# BSPDSchematic.net
KiCad netlist of a schematic drawn in Altium Designer
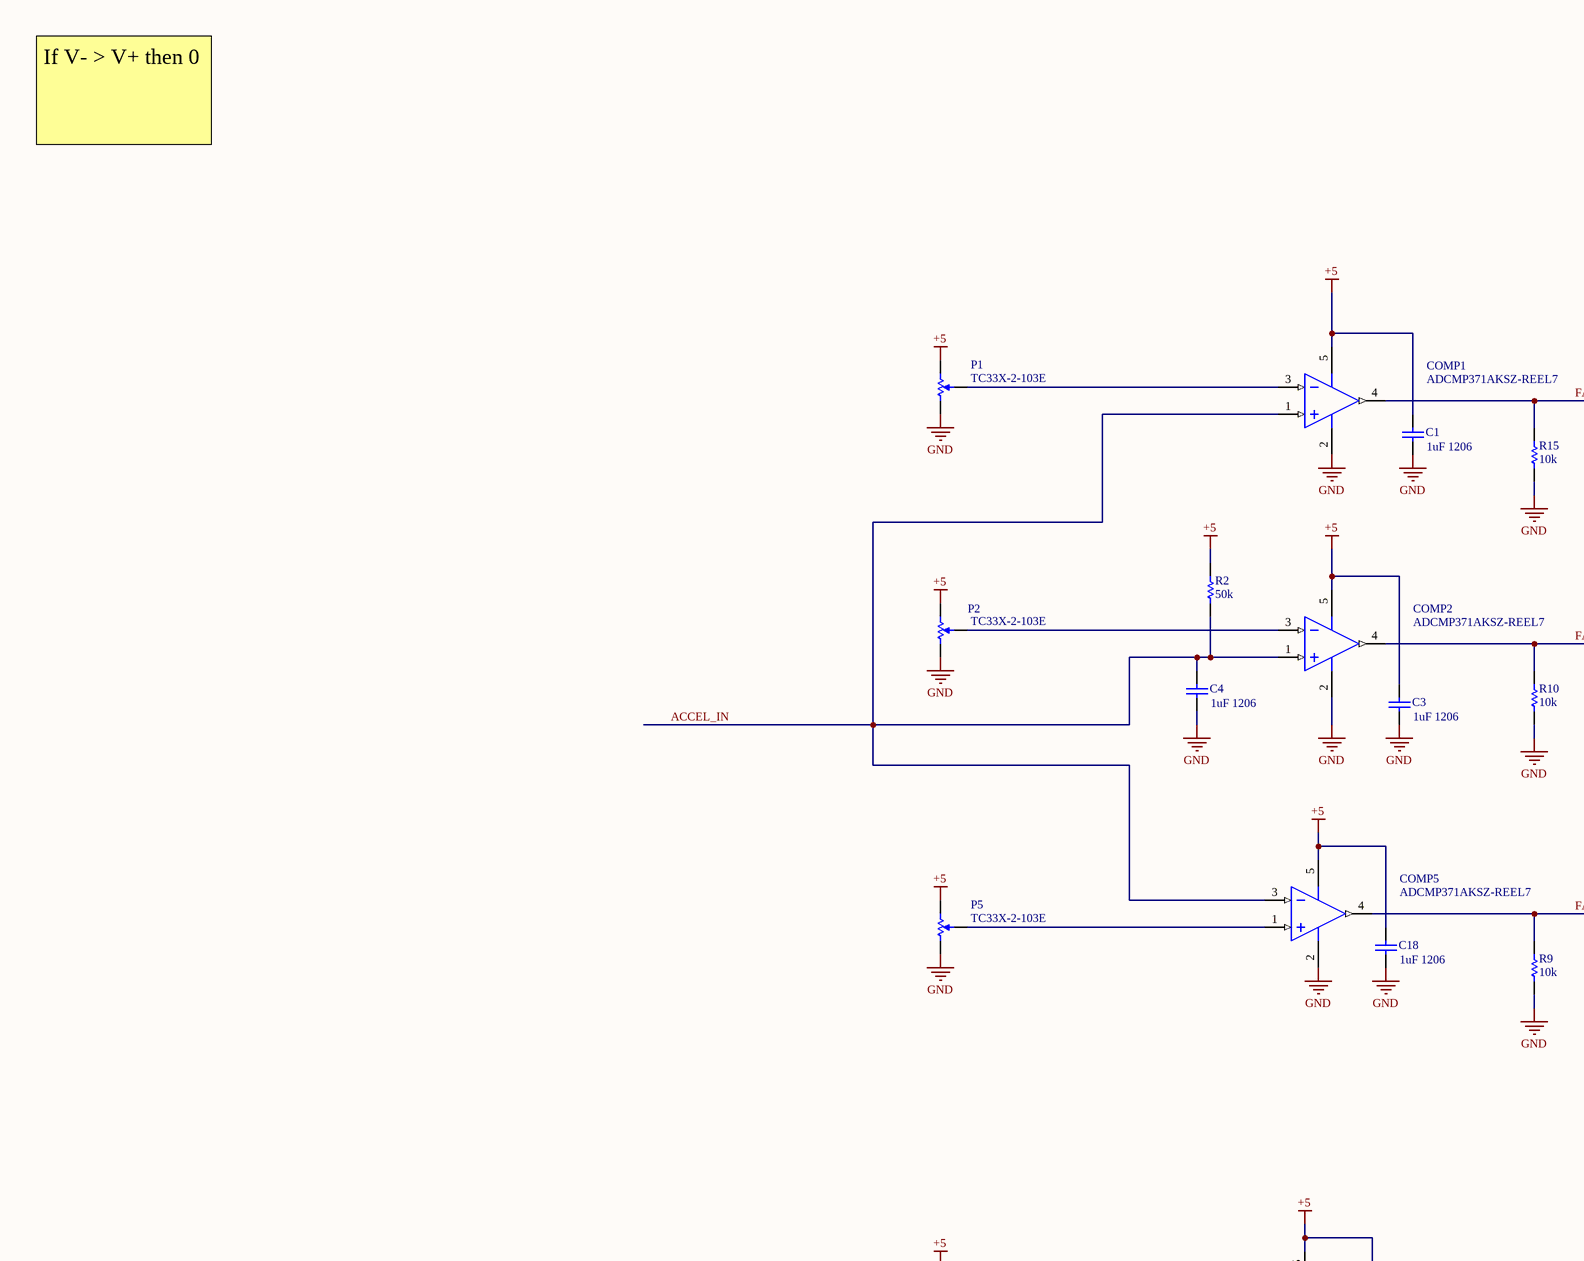
[diagram p0: BSPDSchematic.SchDoc, top left]
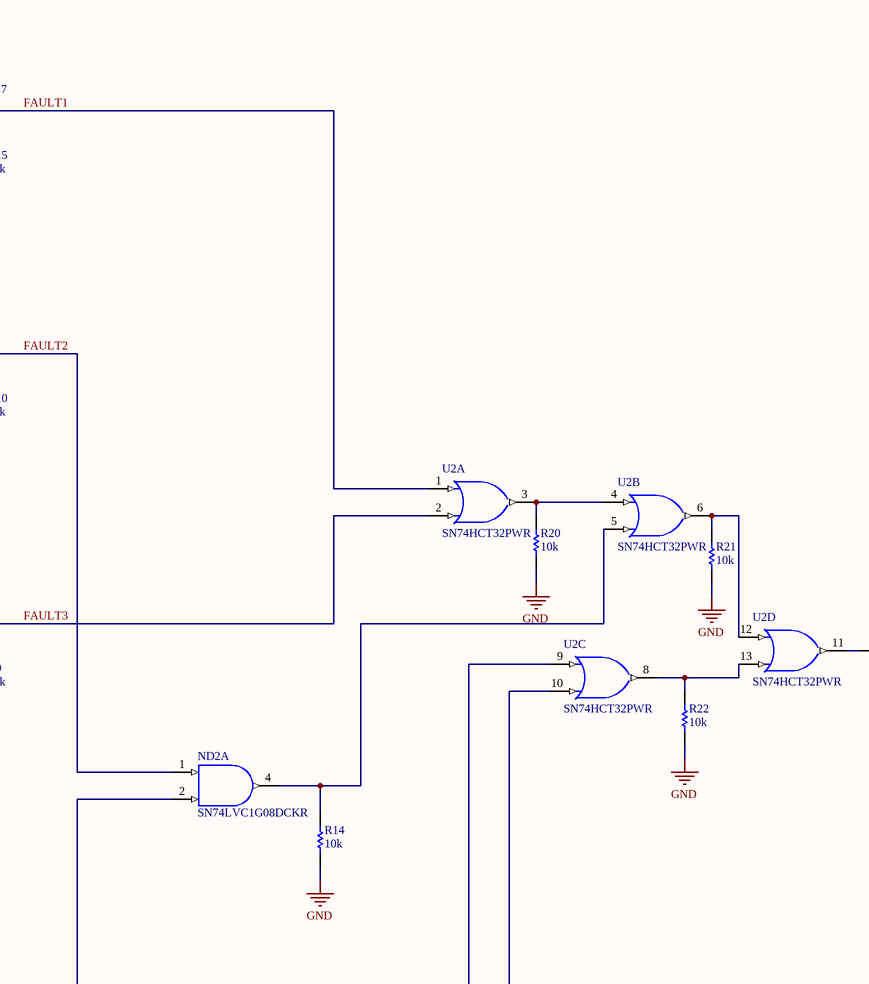
[diagram p1: BSPDSchematic.SchDoc, top middle]
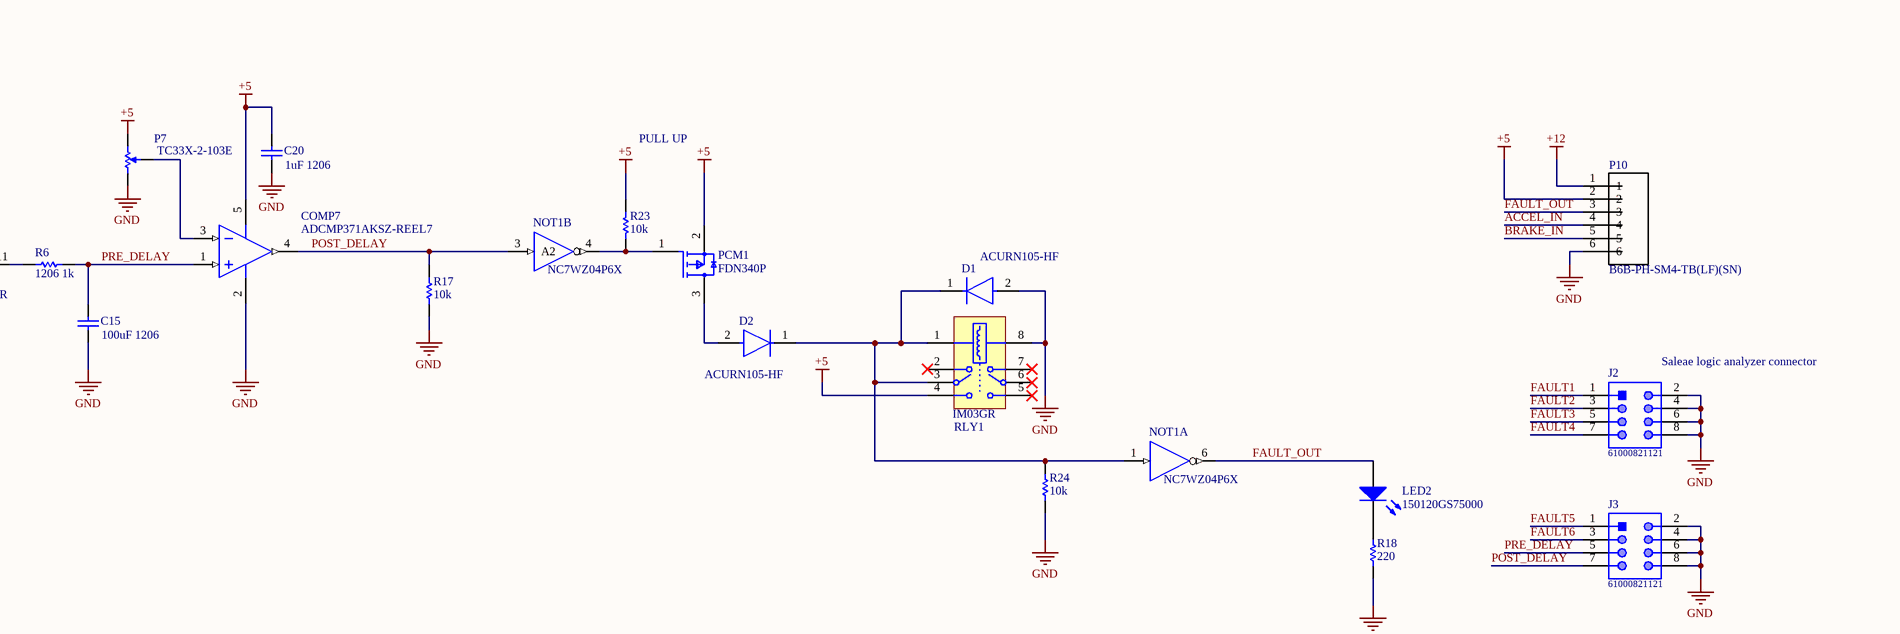
[diagram p2: BSPDSchematic.SchDoc, top right]
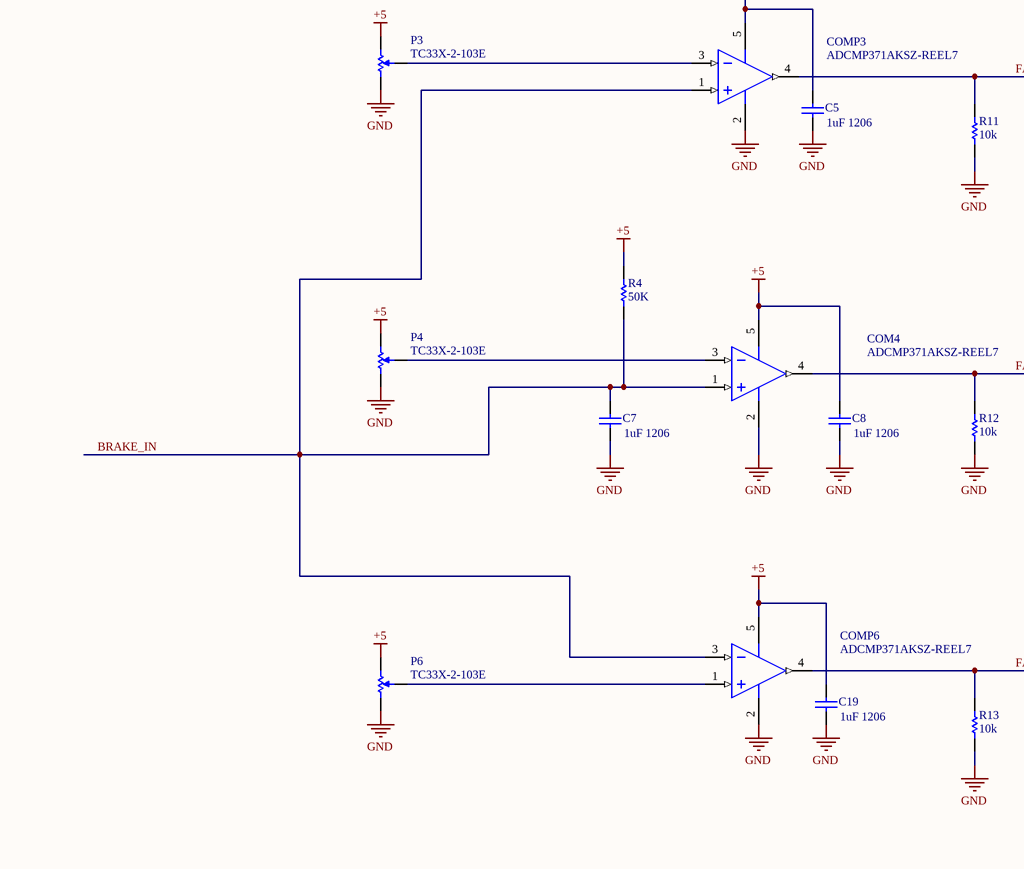
[diagram p3: BSPDSchematic.SchDoc, bottom left]
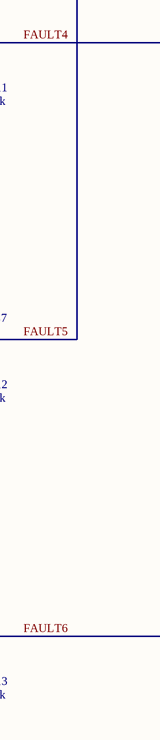
[diagram p4: BSPDSchematic.SchDoc, bottom middle]
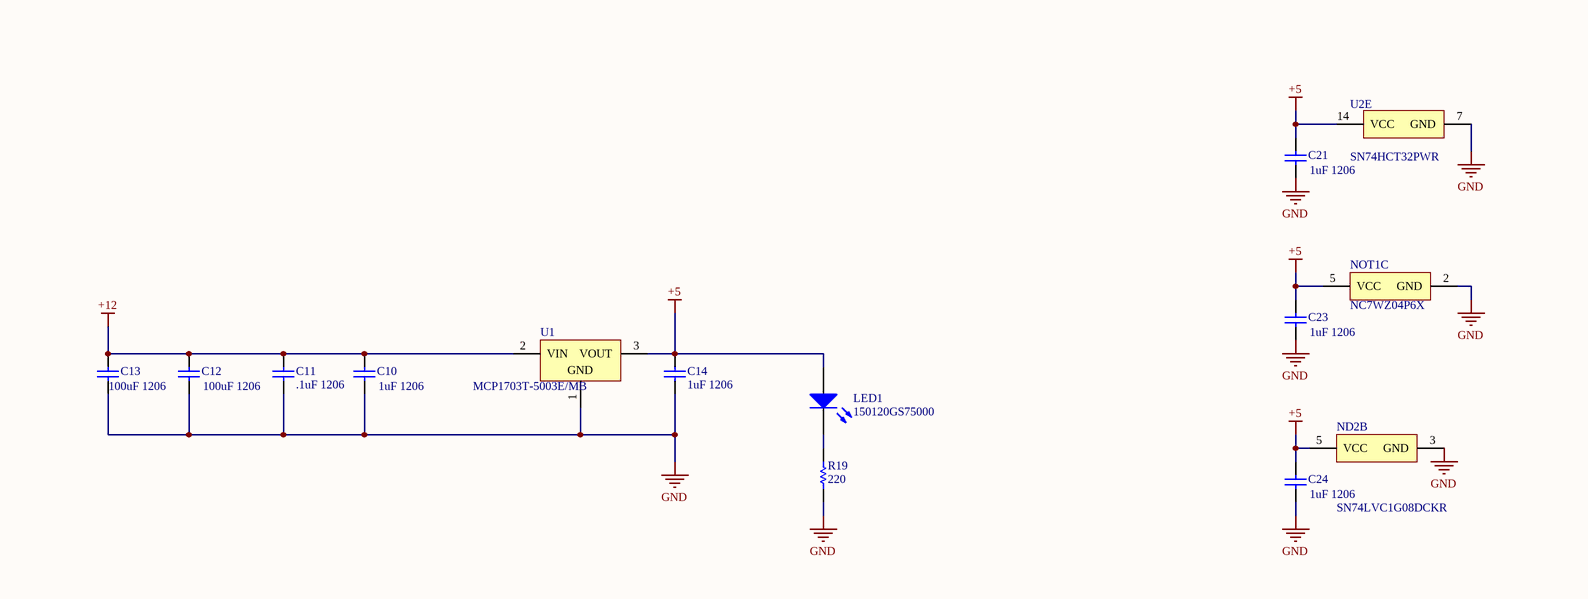
[diagram p5: BSPDSchematic.SchDoc, bottom right]

(export (version "E")
  (design (tool "Eeschema 10.0.6"))
  (components
    (comp (ref "C1")
      (value "1uF 1206")
      (footprint "CAPC3216X152X50LL20T25")
      (description "Chip Capacitor, 330 nF, +/- 10%, 50 V, -55 to 125 degC, 1206 (3216 Metric), RoHS, Tape and Reel")
      (fields (field (name "MANUFACTURER") "AVX"))
      (libsource (lib "Altium Content Vault") (part "CAP-NP-2"))
    )
    (comp (ref "C3")
      (value "1uF 1206")
      (footprint "CAPC3216X152X50LL20T25")
      (description "Chip Capacitor, 330 nF, +/- 10%, 50 V, -55 to 125 degC, 1206 (3216 Metric), RoHS, Tape and Reel")
      (fields (field (name "MANUFACTURER") "AVX"))
      (libsource (lib "Altium Content Vault") (part "CAP-NP-2"))
    )
    (comp (ref "C4")
      (value "1uF 1206")
      (footprint "CAPC3216X152X50LL20T25")
      (description "Chip Capacitor, 330 nF, +/- 10%, 50 V, -55 to 125 degC, 1206 (3216 Metric), RoHS, Tape and Reel")
      (fields (field (name "MANUFACTURER") "AVX"))
      (libsource (lib "Altium Content Vault") (part "CAP-NP-2"))
    )
    (comp (ref "C5")
      (value "1uF 1206")
      (footprint "CAPC3216X152X50LL20T25")
      (description "Chip Capacitor, 330 nF, +/- 10%, 50 V, -55 to 125 degC, 1206 (3216 Metric), RoHS, Tape and Reel")
      (fields (field (name "MANUFACTURER") "AVX"))
      (libsource (lib "Altium Content Vault") (part "CAP-NP-2"))
    )
    (comp (ref "C7")
      (value "1uF 1206")
      (footprint "CAPC3216X152X50LL20T25")
      (description "Chip Capacitor, 330 nF, +/- 10%, 50 V, -55 to 125 degC, 1206 (3216 Metric), RoHS, Tape and Reel")
      (fields (field (name "MANUFACTURER") "AVX"))
      (libsource (lib "Altium Content Vault") (part "CAP-NP-2"))
    )
    (comp (ref "C8")
      (value "1uF 1206")
      (footprint "CAPC3216X152X50LL20T25")
      (description "Chip Capacitor, 330 nF, +/- 10%, 50 V, -55 to 125 degC, 1206 (3216 Metric), RoHS, Tape and Reel")
      (fields (field (name "MANUFACTURER") "AVX"))
      (libsource (lib "Altium Content Vault") (part "CAP-NP-2"))
    )
    (comp (ref "C10")
      (value "1uF 1206")
      (footprint "CAPC3216X152X50LL20T25")
      (description "Chip Capacitor, 330 nF, +/- 10%, 50 V, -55 to 125 degC, 1206 (3216 Metric), RoHS, Tape and Reel")
      (fields (field (name "MANUFACTURER") "AVX"))
      (libsource (lib "Altium Content Vault") (part "CAP-NP-2"))
    )
    (comp (ref "C11")
      (value ".1uF 1206")
      (footprint "CAPC1206(3216)190_L")
      (description "CAP 100uF 6.3V ±20% 1206 (3216 Metric) Thickness 1.9mm SMD")
      (fields (field (name "TOLERANCE") "Â±20%"))
      (libsource (lib "Altium Content Vault") (part "CAP"))
    )
    (comp (ref "C12")
      (value "100uF 1206")
      (footprint "CAPC1206(3216)190_L")
      (description "CAP 100uF 6.3V ±20% 1206 (3216 Metric) Thickness 1.9mm SMD")
      (fields (field (name "TOLERANCE") "Â±20%"))
      (libsource (lib "Altium Content Vault") (part "CAP"))
    )
    (comp (ref "C13")
      (value "100uF 1206")
      (footprint "CAPC3216X180X50LL20T25")
      (description "Chip Capacitor, 2.2 uF, +/- 10%, 16 V, -55 to 125 degC, 1206 (3216 Metric), RoHS, Tape and Reel")
      (fields (field (name "TOLERANCE") "10%") (field (name "MANUFACTURER") "Kemet"))
      (libsource (lib "Altium Content Vault") (part "CAP-NP-2"))
    )
    (comp (ref "C14")
      (value "1uF 1206")
      (footprint "CAPC3216X180X50ML20T25")
      (description "Chip Capacitor, 1 uF, +/- 10%, 25 V, -55 to 125 degC, 1206 (3216 Metric), RoHS, Tape and Reel")
      (fields (field (name "MANUFACTURER") "Kemet") (field (name "TOLERANCE") "10%"))
      (libsource (lib "Altium Content Vault") (part "CAP-NP-2"))
    )
    (comp (ref "C15")
      (value "100uF 1206")
      (footprint "CAPC3216X152X50LL20T25")
      (description "Chip Capacitor, 330 nF, +/- 10%, 50 V, -55 to 125 degC, 1206 (3216 Metric), RoHS, Tape and Reel")
      (fields (field (name "MANUFACTURER") "AVX"))
      (libsource (lib "Altium Content Vault") (part "CAP-NP-2"))
    )
    (comp (ref "C18")
      (value "1uF 1206")
      (footprint "CAPC3216X152X50LL20T25")
      (description "Chip Capacitor, 330 nF, +/- 10%, 50 V, -55 to 125 degC, 1206 (3216 Metric), RoHS, Tape and Reel")
      (fields (field (name "MANUFACTURER") "AVX"))
      (libsource (lib "Altium Content Vault") (part "CAP-NP-2"))
    )
    (comp (ref "C19")
      (value "1uF 1206")
      (footprint "CAPC3216X152X50LL20T25")
      (description "Chip Capacitor, 330 nF, +/- 10%, 50 V, -55 to 125 degC, 1206 (3216 Metric), RoHS, Tape and Reel")
      (fields (field (name "MANUFACTURER") "AVX"))
      (libsource (lib "Altium Content Vault") (part "CAP-NP-2"))
    )
    (comp (ref "C20")
      (value "1uF 1206")
      (footprint "CAPC3216X152X50LL20T25")
      (description "Chip Capacitor, 330 nF, +/- 10%, 50 V, -55 to 125 degC, 1206 (3216 Metric), RoHS, Tape and Reel")
      (fields (field (name "MANUFACTURER") "AVX"))
      (libsource (lib "Altium Content Vault") (part "CAP-NP-2"))
    )
    (comp (ref "C21")
      (value "1uF 1206")
      (footprint "CAPC3216X152X50LL20T25")
      (description "Chip Capacitor, 330 nF, +/- 10%, 50 V, -55 to 125 degC, 1206 (3216 Metric), RoHS, Tape and Reel")
      (fields (field (name "MANUFACTURER") "AVX"))
      (libsource (lib "Altium Content Vault") (part "CAP-NP-2"))
    )
    (comp (ref "C23")
      (value "1uF 1206")
      (footprint "CAPC3216X152X50LL20T25")
      (description "Chip Capacitor, 330 nF, +/- 10%, 50 V, -55 to 125 degC, 1206 (3216 Metric), RoHS, Tape and Reel")
      (fields (field (name "MANUFACTURER") "AVX"))
      (libsource (lib "Altium Content Vault") (part "CAP-NP-2"))
    )
    (comp (ref "C24")
      (value "1uF 1206")
      (footprint "CAPC3216X152X50LL20T25")
      (description "Chip Capacitor, 330 nF, +/- 10%, 50 V, -55 to 125 degC, 1206 (3216 Metric), RoHS, Tape and Reel")
      (fields (field (name "MANUFACTURER") "AVX"))
      (libsource (lib "Altium Content Vault") (part "CAP-NP-2"))
    )
    (comp (ref "COM4")
      (value "ADCMP371AKSZ-REEL7")
      (footprint "ADI-KS-5_L")
      (description "General-Purpose Comparator, 2.25 to 5.5 V, 5 us Delay, Industrial, 5-pin SOT23 (KS-5), Reel")
      (fields (field (name "MANUFACTURER") "Analog Devices"))
      (libsource (lib "Altium Content Vault") (part "ADI-ADCMP371-KS-5"))
    )
    (comp (ref "COMP1")
      (value "ADCMP371AKSZ-REEL7")
      (footprint "ADI-KS-5_L")
      (description "General-Purpose Comparator, 2.25 to 5.5 V, 5 us Delay, Industrial, 5-pin SOT23 (KS-5), Reel")
      (fields (field (name "MANUFACTURER") "Analog Devices"))
      (libsource (lib "Altium Content Vault") (part "ADI-ADCMP371-KS-5"))
    )
    (comp (ref "COMP2")
      (value "ADCMP371AKSZ-REEL7")
      (footprint "ADI-KS-5_L")
      (description "General-Purpose Comparator, 2.25 to 5.5 V, 5 us Delay, Industrial, 5-pin SOT23 (KS-5), Reel")
      (fields (field (name "MANUFACTURER") "Analog Devices"))
      (libsource (lib "Altium Content Vault") (part "ADI-ADCMP371-KS-5"))
    )
    (comp (ref "COMP3")
      (value "ADCMP371AKSZ-REEL7")
      (footprint "ADI-KS-5_L")
      (description "General-Purpose Comparator, 2.25 to 5.5 V, 5 us Delay, Industrial, 5-pin SOT23 (KS-5), Reel")
      (fields (field (name "MANUFACTURER") "Analog Devices"))
      (libsource (lib "Altium Content Vault") (part "ADI-ADCMP371-KS-5"))
    )
    (comp (ref "COMP5")
      (value "ADCMP371AKSZ-REEL7")
      (footprint "ADI-KS-5_L")
      (description "General-Purpose Comparator, 2.25 to 5.5 V, 5 us Delay, Industrial, 5-pin SOT23 (KS-5), Reel")
      (fields (field (name "MANUFACTURER") "Analog Devices"))
      (libsource (lib "Altium Content Vault") (part "ADI-ADCMP371-KS-5"))
    )
    (comp (ref "COMP6")
      (value "ADCMP371AKSZ-REEL7")
      (footprint "ADI-KS-5_L")
      (description "General-Purpose Comparator, 2.25 to 5.5 V, 5 us Delay, Industrial, 5-pin SOT23 (KS-5), Reel")
      (fields (field (name "MANUFACTURER") "Analog Devices"))
      (libsource (lib "Altium Content Vault") (part "ADI-ADCMP371-KS-5"))
    )
    (comp (ref "COMP7")
      (value "ADCMP371AKSZ-REEL7")
      (footprint "ADI-KS-5_L")
      (description "General-Purpose Comparator, 2.25 to 5.5 V, 5 us Delay, Industrial, 5-pin SOT23 (KS-5), Reel")
      (fields (field (name "MANUFACTURER") "Analog Devices"))
      (libsource (lib "Altium Content Vault") (part "ADI-ADCMP371-KS-5"))
    )
    (comp (ref "D1")
      (value "ACURN105-HF")
      (footprint "FP-1206-MFG")
      (description "DIODE GEN PURP 1KV 1A 1206")
      (libsource (lib "Altium Content Vault") (part "d7152d700b627762746794eb795d46e"))
    )
    (comp (ref "D2")
      (value "ACURN105-HF")
      (footprint "FP-1206-MFG")
      (description "DIODE GEN PURP 1KV 1A 1206")
      (libsource (lib "Altium Content Vault") (part "d7152d700b627762746794eb795d46e"))
    )
    (comp (ref "J2")
      (value "61000821121")
      (footprint "61000821121")
      (description "SMT Vertical Pin Header WR-PHD, Pitch 2.54 mm, Dual Row, 8 pins")
      (fields (field (name "MANUFACTURER") "Wurth Elektronik") (field (name "PUBLISHER") "WurthElektronik"))
      (libsource (lib "Altium Content Vault") (part "WE-CN-2P-M-R8"))
    )
    (comp (ref "J3")
      (value "61000821121")
      (footprint "61000821121")
      (description "SMT Vertical Pin Header WR-PHD, Pitch 2.54 mm, Dual Row, 8 pins")
      (fields (field (name "MANUFACTURER") "Wurth Elektronik") (field (name "PUBLISHER") "WurthElektronik"))
      (libsource (lib "Altium Content Vault") (part "WE-CN-2P-M-R8"))
    )
    (comp (ref "LED1")
      (value "150120GS75000")
      (footprint "1206_A")
      (description "SMD mono-color Chip LED, WL-SMCW, Green")
      (fields (field (name "MANUFACTURER") "Wuerth Elektronik"))
      (libsource (lib "Altium Content Vault") (part "WE-LED_K1A2-2"))
    )
    (comp (ref "LED2")
      (value "150120GS75000")
      (footprint "1206_A")
      (description "SMD mono-color Chip LED, WL-SMCW, Green")
      (fields (field (name "MANUFACTURER") "Wuerth Elektronik"))
      (libsource (lib "Altium Content Vault") (part "WE-LED_K1A2-2"))
    )
    (comp (ref "ND2")
      (value "SN74LVC1G08DCKR")
      (footprint "DCK0005A_M")
      (description "Single 2-Input Positive-AND Gate, DCK0005A, LARGE T&R")
      (fields
        (field (name "GENERIC PART NUMBER") "SN74LVC1G08")
        (field (name "MANUFACTURER") "Texas Instruments")
      )
      (libsource (lib "Altium Content Vault") (part "TI-SN74XXX1X08-5"))
    )
    (comp (ref "NOT1")
      (value "NC7WZ04P6X")
      (footprint "FAIR-SC70-6_V")
      (fields (field (name "MANUFACTURER") "Fairchild Semiconductor"))
      (libsource (lib "Altium Content Vault") (part "FAIR-NC7WZ04-SC70-6"))
    )
    (comp (ref "P1")
      (value "TC33X-2-103E")
      (footprint "BOUR-TC33X-2_V")
      (description "Trimming Potentiometer, 10000 Ohm, -40 to 100 degC, 3-Pin SMD, RoHS, Tape and Reel")
      (fields (field (name "TOLERANCE") "25%") (field (name "MANUFACTURER") "Bourns"))
      (libsource (lib "Altium Content Vault") (part "RES-ADJ-3_A"))
    )
    (comp (ref "P2")
      (value "TC33X-2-103E")
      (footprint "BOUR-TC33X-2_V")
      (description "Trimming Potentiometer, 10000 Ohm, -40 to 100 degC, 3-Pin SMD, RoHS, Tape and Reel")
      (fields (field (name "TOLERANCE") "25%") (field (name "MANUFACTURER") "Bourns"))
      (libsource (lib "Altium Content Vault") (part "RES-ADJ-3_A"))
    )
    (comp (ref "P3")
      (value "TC33X-2-103E")
      (footprint "BOUR-TC33X-2_V")
      (description "Trimming Potentiometer, 10000 Ohm, -40 to 100 degC, 3-Pin SMD, RoHS, Tape and Reel")
      (fields (field (name "TOLERANCE") "25%") (field (name "MANUFACTURER") "Bourns"))
      (libsource (lib "Altium Content Vault") (part "RES-ADJ-3_A"))
    )
    (comp (ref "P4")
      (value "TC33X-2-103E")
      (footprint "BOUR-TC33X-2_V")
      (description "Trimming Potentiometer, 10000 Ohm, -40 to 100 degC, 3-Pin SMD, RoHS, Tape and Reel")
      (fields (field (name "TOLERANCE") "25%") (field (name "MANUFACTURER") "Bourns"))
      (libsource (lib "Altium Content Vault") (part "RES-ADJ-3_A"))
    )
    (comp (ref "P5")
      (value "TC33X-2-103E")
      (footprint "BOUR-TC33X-2_V")
      (description "Trimming Potentiometer, 10000 Ohm, -40 to 100 degC, 3-Pin SMD, RoHS, Tape and Reel")
      (fields (field (name "TOLERANCE") "25%") (field (name "MANUFACTURER") "Bourns"))
      (libsource (lib "Altium Content Vault") (part "RES-ADJ-3_A"))
    )
    (comp (ref "P6")
      (value "TC33X-2-103E")
      (footprint "BOUR-TC33X-2_V")
      (description "Trimming Potentiometer, 10000 Ohm, -40 to 100 degC, 3-Pin SMD, RoHS, Tape and Reel")
      (fields (field (name "TOLERANCE") "25%") (field (name "MANUFACTURER") "Bourns"))
      (libsource (lib "Altium Content Vault") (part "RES-ADJ-3_A"))
    )
    (comp (ref "P7")
      (value "TC33X-2-103E")
      (footprint "BOUR-TC33X-2_V")
      (description "Trimming Potentiometer, 10000 Ohm, -40 to 100 degC, 3-Pin SMD, RoHS, Tape and Reel")
      (fields (field (name "TOLERANCE") "25%") (field (name "MANUFACTURER") "Bourns"))
      (libsource (lib "Altium Content Vault") (part "RES-ADJ-3_A"))
    )
    (comp (ref "P10")
      (value "B6B-PH-SM4-TB(LF)(SN)")
      (footprint "*JST_B6B-PH-SM4-TB(LF)(SN)")
      (description "Connector Header Surface Mount 6 position 0.079 _2.00mm_")
      (fields (field (name "MP") "B6B-PH-SM4-TB_LF__SN_") (field (name "MF") "JST Sales"))
      (libsource (lib "B6B-PH-SM4-TB_LF__SN_") (part "B6B-PH-SM4-TB(LF)(SN)"))
    )
    (comp (ref "PCM1")
      (value "FDN340P")
      (footprint "FP-527AG-MFG")
      (description "MOSFET P-CH 20V 2A SSOT3")
      (libsource (lib "Altium Content Vault") (part "d23f43cc42f60b967b7caccf14518fd"))
    )
    (comp (ref "R2")
      (value "50k")
      (footprint "RESC3216X60X45ML10T20")
      (fields (field (name "MANUFACTURER") "Vishay Dale") (field (name "PART NUMBER") "CRCW1206220RFKEA"))
      (libsource (lib "Altium Content Vault") (part "RES"))
    )
    (comp (ref "R4")
      (value "50K")
      (footprint "RESC3216X60X45ML10T20")
      (fields (field (name "MANUFACTURER") "Vishay Dale") (field (name "PART NUMBER") "CRCW1206220RFKEA"))
      (libsource (lib "Altium Content Vault") (part "RES"))
    )
    (comp (ref "R6")
      (value "1206 1k")
      (footprint "RESC3216X60X45ML10T20")
      (fields (field (name "MANUFACTURER") "Vishay Dale") (field (name "PART NUMBER") "CRCW1206220RFKEA"))
      (libsource (lib "Altium Content Vault") (part "RES"))
    )
    (comp (ref "R9")
      (value "10k")
      (footprint "RESC3216X60X45ML10T20")
      (fields (field (name "MANUFACTURER") "Vishay Dale") (field (name "PART NUMBER") "CRCW1206220RFKEA"))
      (libsource (lib "Altium Content Vault") (part "RES"))
    )
    (comp (ref "R10")
      (value "10k")
      (footprint "RESC3216X60X45ML10T20")
      (fields (field (name "MANUFACTURER") "Vishay Dale") (field (name "PART NUMBER") "CRCW1206220RFKEA"))
      (libsource (lib "Altium Content Vault") (part "RES"))
    )
    (comp (ref "R11")
      (value "10k")
      (footprint "RESC3216X60X45ML10T20")
      (fields (field (name "MANUFACTURER") "Vishay Dale") (field (name "PART NUMBER") "CRCW1206220RFKEA"))
      (libsource (lib "Altium Content Vault") (part "RES"))
    )
    (comp (ref "R12")
      (value "10k")
      (footprint "RESC3216X60X45ML10T20")
      (fields (field (name "MANUFACTURER") "Vishay Dale") (field (name "PART NUMBER") "CRCW1206220RFKEA"))
      (libsource (lib "Altium Content Vault") (part "RES"))
    )
    (comp (ref "R13")
      (value "10k")
      (footprint "RESC3216X60X45ML10T20")
      (fields (field (name "MANUFACTURER") "Vishay Dale") (field (name "PART NUMBER") "CRCW1206220RFKEA"))
      (libsource (lib "Altium Content Vault") (part "RES"))
    )
    (comp (ref "R14")
      (value "10k")
      (footprint "RESC3216X60X45ML10T20")
      (fields (field (name "MANUFACTURER") "Vishay Dale") (field (name "PART NUMBER") "CRCW1206220RFKEA"))
      (libsource (lib "Altium Content Vault") (part "RES"))
    )
    (comp (ref "R15")
      (value "10k")
      (footprint "RESC3216X60X45ML10T20")
      (fields (field (name "MANUFACTURER") "Vishay Dale") (field (name "PART NUMBER") "CRCW1206220RFKEA"))
      (libsource (lib "Altium Content Vault") (part "RES"))
    )
    (comp (ref "R17")
      (value "10k")
      (footprint "RESC3216X60X45ML10T20")
      (fields (field (name "MANUFACTURER") "Vishay Dale") (field (name "PART NUMBER") "CRCW1206220RFKEA"))
      (libsource (lib "Altium Content Vault") (part "RES"))
    )
    (comp (ref "R18")
      (value "220")
      (footprint "RESC3216X60X45ML10T20")
      (fields (field (name "MANUFACTURER") "Vishay Dale") (field (name "PART NUMBER") "CRCW1206220RFKEA"))
      (libsource (lib "Altium Content Vault") (part "RES"))
    )
    (comp (ref "R19")
      (value "220")
      (footprint "RESC3216X60X45ML10T20")
      (fields (field (name "MANUFACTURER") "Vishay Dale") (field (name "PART NUMBER") "CRCW1206220RFKEA"))
      (libsource (lib "Altium Content Vault") (part "RES"))
    )
    (comp (ref "R20")
      (value "10k")
      (footprint "RESC3216X60X45ML10T20")
      (fields (field (name "MANUFACTURER") "Vishay Dale") (field (name "PART NUMBER") "CRCW1206220RFKEA"))
      (libsource (lib "Altium Content Vault") (part "RES"))
    )
    (comp (ref "R21")
      (value "10k")
      (footprint "RESC3216X60X45ML10T20")
      (fields (field (name "MANUFACTURER") "Vishay Dale") (field (name "PART NUMBER") "CRCW1206220RFKEA"))
      (libsource (lib "Altium Content Vault") (part "RES"))
    )
    (comp (ref "R22")
      (value "10k")
      (footprint "RESC3216X60X45ML10T20")
      (fields (field (name "MANUFACTURER") "Vishay Dale") (field (name "PART NUMBER") "CRCW1206220RFKEA"))
      (libsource (lib "Altium Content Vault") (part "RES"))
    )
    (comp (ref "R23")
      (value "10k")
      (footprint "RESC3216X60X45ML10T20")
      (fields (field (name "MANUFACTURER") "Vishay Dale") (field (name "PART NUMBER") "CRCW1206220RFKEA"))
      (libsource (lib "Altium Content Vault") (part "RES"))
    )
    (comp (ref "R24")
      (value "10k")
      (footprint "RESC3216X60X45ML10T20")
      (fields (field (name "MANUFACTURER") "Vishay Dale") (field (name "PART NUMBER") "CRCW1206220RFKEA"))
      (libsource (lib "Altium Content Vault") (part "RES"))
    )
    (comp (ref "RLY1")
      (value "IM03GR")
      (footprint "TECO-IM-8G-WING")
      (description "Low Power Consumption, High Dielectric, High Mechanical Shock Resistance, IM Relay")
      (fields (field (name "MANUFACTURER") "TE Connectivity"))
      (libsource (lib "Altium Content Vault") (part "TECO-IM03GR"))
    )
    (comp (ref "U1")
      (value "MCP1703T-5003E/MB")
      (footprint "SOT-89_L")
      (description "IC REG LINEAR 5V 100MA SOT89-3")
      (libsource (lib "Altium Content Vault") (part "PM-REG-7905-SIL3A"))
    )
    (comp (ref "U2")
      (value "SN74HCT32PWR")
      (footprint "PW0014A_N")
      (description "Quadruple 2-Input Positive-OR Gates, PW0014A, LARGE T&R")
      (fields
        (field (name "MANUFACTURER") "Texas Instruments")
        (field (name "GENERIC PART NUMBER") "SN74HCT32")
      )
      (libsource (lib "Altium Content Vault") (part "TI-OR-4-2IN-14"))
    )
  )
  (nets
    (net (code "1") (name "+5") (class "Default")
      (node (ref "C1") (pin "2") (pinfunction "2_2") (pintype "passive"))
      (node (ref "C14") (pin "2") (pinfunction "2_2") (pintype "passive"))
      (node (ref "C18") (pin "2") (pinfunction "2_2") (pintype "passive"))
      (node (ref "C19") (pin "2") (pinfunction "2_2") (pintype "passive"))
      (node (ref "C20") (pin "2") (pinfunction "2_2") (pintype "passive"))
      (node (ref "C21") (pin "2") (pinfunction "2_2") (pintype "passive"))
      (node (ref "C23") (pin "2") (pinfunction "2_2") (pintype "passive"))
      (node (ref "C24") (pin "2") (pinfunction "2_2") (pintype "passive"))
      (node (ref "C3") (pin "2") (pinfunction "2_2") (pintype "passive"))
      (node (ref "C5") (pin "2") (pinfunction "2_2") (pintype "passive"))
      (node (ref "C8") (pin "2") (pinfunction "2_2") (pintype "passive"))
      (node (ref "COM4") (pin "5") (pinfunction "VCC_5") (pintype "power_in"))
      (node (ref "COMP1") (pin "5") (pinfunction "VCC_5") (pintype "power_in"))
      (node (ref "COMP2") (pin "5") (pinfunction "VCC_5") (pintype "power_in"))
      (node (ref "COMP3") (pin "5") (pinfunction "VCC_5") (pintype "power_in"))
      (node (ref "COMP5") (pin "5") (pinfunction "VCC_5") (pintype "power_in"))
      (node (ref "COMP6") (pin "5") (pinfunction "VCC_5") (pintype "power_in"))
      (node (ref "COMP7") (pin "5") (pinfunction "VCC_5") (pintype "power_in"))
      (node (ref "LED1") (pin "2") (pinfunction "A_2") (pintype "passive"))
      (node (ref "ND2") (pin "5") (pinfunction "VCC_5") (pintype "power_in"))
      (node (ref "NOT1") (pin "5") (pinfunction "VCC_5") (pintype "power_in"))
      (node (ref "P1") (pin "3") (pinfunction "3_3") (pintype "passive"))
      (node (ref "P10") (pin "2") (pinfunction "2_2") (pintype "passive"))
      (node (ref "P2") (pin "3") (pinfunction "3_3") (pintype "passive"))
      (node (ref "P3") (pin "3") (pinfunction "3_3") (pintype "passive"))
      (node (ref "P4") (pin "3") (pinfunction "3_3") (pintype "passive"))
      (node (ref "P5") (pin "3") (pinfunction "3_3") (pintype "passive"))
      (node (ref "P6") (pin "3") (pinfunction "3_3") (pintype "passive"))
      (node (ref "P7") (pin "3") (pinfunction "3_3") (pintype "passive"))
      (node (ref "PCM1") (pin "2") (pinfunction "S_2") (pintype "passive"))
      (node (ref "R2") (pin "1") (pinfunction "1_1") (pintype "passive"))
      (node (ref "R23") (pin "2") (pinfunction "2_2") (pintype "passive"))
      (node (ref "R4") (pin "1") (pinfunction "1_1") (pintype "passive"))
      (node (ref "RLY1") (pin "4") (pinfunction "4_4") (pintype "passive"))
      (node (ref "U1") (pin "3") (pinfunction "VOUT_3") (pintype "power_in"))
      (node (ref "U2") (pin "14") (pinfunction "VCC_14") (pintype "power_in"))
    )
    (net (code "2") (name "+12") (class "Default")
      (node (ref "C10") (pin "2") (pinfunction "2_2") (pintype "passive"))
      (node (ref "C11") (pin "2") (pinfunction "2_2") (pintype "passive"))
      (node (ref "C12") (pin "2") (pinfunction "2_2") (pintype "passive"))
      (node (ref "C13") (pin "2") (pinfunction "2_2") (pintype "passive"))
      (node (ref "P10") (pin "1") (pinfunction "1_1") (pintype "passive"))
      (node (ref "U1") (pin "2") (pinfunction "VIN_2") (pintype "power_in"))
    )
    (net (code "3") (name "/ACCEL_IN") (class "Default")
      (node (ref "C4") (pin "2") (pinfunction "2_2") (pintype "passive"))
      (node (ref "COMP1") (pin "1") (pinfunction "IN+_1") (pintype "input"))
      (node (ref "COMP2") (pin "1") (pinfunction "IN+_1") (pintype "input"))
      (node (ref "COMP5") (pin "3") (pinfunction "IN-_3") (pintype "input"))
      (node (ref "P10") (pin "4") (pinfunction "4_4") (pintype "passive"))
      (node (ref "R2") (pin "2") (pinfunction "2_2") (pintype "passive"))
    )
    (net (code "4") (name "/BRAKE_IN") (class "Default")
      (node (ref "C7") (pin "2") (pinfunction "2_2") (pintype "passive"))
      (node (ref "COM4") (pin "1") (pinfunction "IN+_1") (pintype "input"))
      (node (ref "COMP3") (pin "1") (pinfunction "IN+_1") (pintype "input"))
      (node (ref "COMP6") (pin "3") (pinfunction "IN-_3") (pintype "input"))
      (node (ref "P10") (pin "5") (pinfunction "5_5") (pintype "passive"))
      (node (ref "R4") (pin "2") (pinfunction "2_2") (pintype "passive"))
    )
    (net (code "5") (name "/FAULT1") (class "Default")
      (node (ref "COMP1") (pin "4") (pinfunction "OUT_4") (pintype "output"))
      (node (ref "J2") (pin "1") (pinfunction "1_1") (pintype "passive"))
      (node (ref "R15") (pin "1") (pinfunction "1_1") (pintype "passive"))
      (node (ref "U2") (pin "1") (pinfunction "1A_1") (pintype "input"))
    )
    (net (code "6") (name "/FAULT2") (class "Default")
      (node (ref "COMP2") (pin "4") (pinfunction "OUT_4") (pintype "output"))
      (node (ref "J2") (pin "3") (pinfunction "3_3") (pintype "passive"))
      (node (ref "ND2") (pin "1") (pinfunction "A_1") (pintype "input"))
      (node (ref "R10") (pin "1") (pinfunction "1_1") (pintype "passive"))
    )
    (net (code "7") (name "/FAULT3") (class "Default")
      (node (ref "COMP5") (pin "4") (pinfunction "OUT_4") (pintype "output"))
      (node (ref "J2") (pin "5") (pinfunction "5_5") (pintype "passive"))
      (node (ref "R9") (pin "1") (pinfunction "1_1") (pintype "passive"))
      (node (ref "U2") (pin "2") (pinfunction "1B_2") (pintype "input"))
    )
    (net (code "8") (name "/FAULT4") (class "Default")
      (node (ref "COMP3") (pin "4") (pinfunction "OUT_4") (pintype "output"))
      (node (ref "J2") (pin "7") (pinfunction "7_7") (pintype "passive"))
      (node (ref "R11") (pin "1") (pinfunction "1_1") (pintype "passive"))
      (node (ref "U2") (pin "9") (pinfunction "3A_9") (pintype "input"))
    )
    (net (code "9") (name "/FAULT5") (class "Default")
      (node (ref "COM4") (pin "4") (pinfunction "OUT_4") (pintype "output"))
      (node (ref "J3") (pin "1") (pinfunction "1_1") (pintype "passive"))
      (node (ref "ND2") (pin "2") (pinfunction "B_2") (pintype "input"))
      (node (ref "R12") (pin "1") (pinfunction "1_1") (pintype "passive"))
    )
    (net (code "10") (name "/FAULT6") (class "Default")
      (node (ref "COMP6") (pin "4") (pinfunction "OUT_4") (pintype "output"))
      (node (ref "J3") (pin "3") (pinfunction "3_3") (pintype "passive"))
      (node (ref "R13") (pin "1") (pinfunction "1_1") (pintype "passive"))
      (node (ref "U2") (pin "10") (pinfunction "3B_10") (pintype "input"))
    )
    (net (code "11") (name "/FAULT_OUT") (class "Default")
      (node (ref "LED2") (pin "2") (pinfunction "A_2") (pintype "passive"))
      (node (ref "NOT1") (pin "6") (pinfunction "Y1_6") (pintype "output"))
      (node (ref "P10") (pin "3") (pinfunction "3_3") (pintype "passive"))
    )
    (net (code "12") (name "/POST_DELAY") (class "Default")
      (node (ref "COMP7") (pin "4") (pinfunction "OUT_4") (pintype "output"))
      (node (ref "J3") (pin "7") (pinfunction "7_7") (pintype "passive"))
      (node (ref "NOT1") (pin "3") (pinfunction "A2_3") (pintype "input"))
      (node (ref "R17") (pin "1") (pinfunction "1_1") (pintype "passive"))
    )
    (net (code "13") (name "/PRE_DELAY") (class "Default")
      (node (ref "C15") (pin "2") (pinfunction "2_2") (pintype "passive"))
      (node (ref "COMP7") (pin "1") (pinfunction "IN+_1") (pintype "input"))
      (node (ref "J3") (pin "5") (pinfunction "5_5") (pintype "passive"))
      (node (ref "R6") (pin "2") (pinfunction "2_2") (pintype "passive"))
    )
    (net (code "14") (name "GND") (class "Default")
      (node (ref "C1") (pin "1") (pinfunction "1_1") (pintype "passive"))
      (node (ref "C10") (pin "1") (pinfunction "1_1") (pintype "passive"))
      (node (ref "C11") (pin "1") (pinfunction "1_1") (pintype "passive"))
      (node (ref "C12") (pin "1") (pinfunction "1_1") (pintype "passive"))
      (node (ref "C13") (pin "1") (pinfunction "1_1") (pintype "passive"))
      (node (ref "C14") (pin "1") (pinfunction "1_1") (pintype "passive"))
      (node (ref "C15") (pin "1") (pinfunction "1_1") (pintype "passive"))
      (node (ref "C18") (pin "1") (pinfunction "1_1") (pintype "passive"))
      (node (ref "C19") (pin "1") (pinfunction "1_1") (pintype "passive"))
      (node (ref "C20") (pin "1") (pinfunction "1_1") (pintype "passive"))
      (node (ref "C21") (pin "1") (pinfunction "1_1") (pintype "passive"))
      (node (ref "C23") (pin "1") (pinfunction "1_1") (pintype "passive"))
      (node (ref "C24") (pin "1") (pinfunction "1_1") (pintype "passive"))
      (node (ref "C3") (pin "1") (pinfunction "1_1") (pintype "passive"))
      (node (ref "C4") (pin "1") (pinfunction "1_1") (pintype "passive"))
      (node (ref "C5") (pin "1") (pinfunction "1_1") (pintype "passive"))
      (node (ref "C7") (pin "1") (pinfunction "1_1") (pintype "passive"))
      (node (ref "C8") (pin "1") (pinfunction "1_1") (pintype "passive"))
      (node (ref "COM4") (pin "2") (pinfunction "GND_2") (pintype "power_in"))
      (node (ref "COMP1") (pin "2") (pinfunction "GND_2") (pintype "power_in"))
      (node (ref "COMP2") (pin "2") (pinfunction "GND_2") (pintype "power_in"))
      (node (ref "COMP3") (pin "2") (pinfunction "GND_2") (pintype "power_in"))
      (node (ref "COMP5") (pin "2") (pinfunction "GND_2") (pintype "power_in"))
      (node (ref "COMP6") (pin "2") (pinfunction "GND_2") (pintype "power_in"))
      (node (ref "COMP7") (pin "2") (pinfunction "GND_2") (pintype "power_in"))
      (node (ref "D1") (pin "2") (pinfunction "A_2") (pintype "passive"))
      (node (ref "J2") (pin "2") (pinfunction "2_2") (pintype "passive"))
      (node (ref "J2") (pin "4") (pinfunction "4_4") (pintype "passive"))
      (node (ref "J2") (pin "6") (pinfunction "6_6") (pintype "passive"))
      (node (ref "J2") (pin "8") (pinfunction "8_8") (pintype "passive"))
      (node (ref "J3") (pin "2") (pinfunction "2_2") (pintype "passive"))
      (node (ref "J3") (pin "4") (pinfunction "4_4") (pintype "passive"))
      (node (ref "J3") (pin "6") (pinfunction "6_6") (pintype "passive"))
      (node (ref "J3") (pin "8") (pinfunction "8_8") (pintype "passive"))
      (node (ref "ND2") (pin "3") (pinfunction "GND_3") (pintype "power_in"))
      (node (ref "NOT1") (pin "2") (pinfunction "GND_2") (pintype "power_in"))
      (node (ref "P1") (pin "1") (pinfunction "1_1") (pintype "passive"))
      (node (ref "P10") (pin "6") (pinfunction "6_6") (pintype "passive"))
      (node (ref "P2") (pin "1") (pinfunction "1_1") (pintype "passive"))
      (node (ref "P3") (pin "1") (pinfunction "1_1") (pintype "passive"))
      (node (ref "P4") (pin "1") (pinfunction "1_1") (pintype "passive"))
      (node (ref "P5") (pin "1") (pinfunction "1_1") (pintype "passive"))
      (node (ref "P6") (pin "1") (pinfunction "1_1") (pintype "passive"))
      (node (ref "P7") (pin "1") (pinfunction "1_1") (pintype "passive"))
      (node (ref "R10") (pin "2") (pinfunction "2_2") (pintype "passive"))
      (node (ref "R11") (pin "2") (pinfunction "2_2") (pintype "passive"))
      (node (ref "R12") (pin "2") (pinfunction "2_2") (pintype "passive"))
      (node (ref "R13") (pin "2") (pinfunction "2_2") (pintype "passive"))
      (node (ref "R14") (pin "2") (pinfunction "2_2") (pintype "passive"))
      (node (ref "R15") (pin "2") (pinfunction "2_2") (pintype "passive"))
      (node (ref "R17") (pin "2") (pinfunction "2_2") (pintype "passive"))
      (node (ref "R18") (pin "2") (pinfunction "2_2") (pintype "passive"))
      (node (ref "R19") (pin "2") (pinfunction "2_2") (pintype "passive"))
      (node (ref "R20") (pin "2") (pinfunction "2_2") (pintype "passive"))
      (node (ref "R21") (pin "2") (pinfunction "2_2") (pintype "passive"))
      (node (ref "R22") (pin "2") (pinfunction "2_2") (pintype "passive"))
      (node (ref "R24") (pin "2") (pinfunction "2_2") (pintype "passive"))
      (node (ref "R9") (pin "2") (pinfunction "2_2") (pintype "passive"))
      (node (ref "RLY1") (pin "8") (pinfunction "8_8") (pintype "passive"))
      (node (ref "U1") (pin "1") (pinfunction "GND_1") (pintype "power_in"))
      (node (ref "U2") (pin "7") (pinfunction "GND_7") (pintype "power_in"))
    )
    (net (code "15") (name "Net-(COM4-IN-)") (class "Default")
      (node (ref "COM4") (pin "3") (pinfunction "IN-_3") (pintype "input"))
      (node (ref "P4") (pin "2") (pinfunction "2_2") (pintype "passive"))
    )
    (net (code "16") (name "Net-(COMP1-IN-)") (class "Default")
      (node (ref "COMP1") (pin "3") (pinfunction "IN-_3") (pintype "input"))
      (node (ref "P1") (pin "2") (pinfunction "2_2") (pintype "passive"))
    )
    (net (code "17") (name "Net-(COMP2-IN-)") (class "Default")
      (node (ref "COMP2") (pin "3") (pinfunction "IN-_3") (pintype "input"))
      (node (ref "P2") (pin "2") (pinfunction "2_2") (pintype "passive"))
    )
    (net (code "18") (name "Net-(COMP3-IN-)") (class "Default")
      (node (ref "COMP3") (pin "3") (pinfunction "IN-_3") (pintype "input"))
      (node (ref "P3") (pin "2") (pinfunction "2_2") (pintype "passive"))
    )
    (net (code "19") (name "Net-(COMP5-IN+)") (class "Default")
      (node (ref "COMP5") (pin "1") (pinfunction "IN+_1") (pintype "input"))
      (node (ref "P5") (pin "2") (pinfunction "2_2") (pintype "passive"))
    )
    (net (code "20") (name "Net-(COMP6-IN+)") (class "Default")
      (node (ref "COMP6") (pin "1") (pinfunction "IN+_1") (pintype "input"))
      (node (ref "P6") (pin "2") (pinfunction "2_2") (pintype "passive"))
    )
    (net (code "21") (name "Net-(COMP7-IN-)") (class "Default")
      (node (ref "COMP7") (pin "3") (pinfunction "IN-_3") (pintype "input"))
      (node (ref "P7") (pin "2") (pinfunction "2_2") (pintype "passive"))
    )
    (net (code "22") (name "Net-(D1-C)") (class "Default")
      (node (ref "D1") (pin "1") (pinfunction "C_1") (pintype "passive"))
      (node (ref "D2") (pin "1") (pinfunction "C_1") (pintype "passive"))
      (node (ref "NOT1") (pin "1") (pinfunction "A1_1") (pintype "input"))
      (node (ref "R24") (pin "1") (pinfunction "1_1") (pintype "passive"))
      (node (ref "RLY1") (pin "1") (pinfunction "1_1") (pintype "passive"))
      (node (ref "RLY1") (pin "3") (pinfunction "3_3") (pintype "passive"))
    )
    (net (code "23") (name "Net-(D2-A)") (class "Default")
      (node (ref "D2") (pin "2") (pinfunction "A_2") (pintype "passive"))
      (node (ref "PCM1") (pin "3") (pinfunction "D_3") (pintype "passive"))
    )
    (net (code "24") (name "Net-(LED1-K)") (class "Default")
      (node (ref "LED1") (pin "1") (pinfunction "K_1") (pintype "passive"))
      (node (ref "R19") (pin "1") (pinfunction "1_1") (pintype "passive"))
    )
    (net (code "25") (name "Net-(LED2-K)") (class "Default")
      (node (ref "LED2") (pin "1") (pinfunction "K_1") (pintype "passive"))
      (node (ref "R18") (pin "1") (pinfunction "1_1") (pintype "passive"))
    )
    (net (code "26") (name "Net-(ND2A-Y)") (class "Default")
      (node (ref "ND2") (pin "4") (pinfunction "Y_4") (pintype "output"))
      (node (ref "R14") (pin "1") (pinfunction "1_1") (pintype "passive"))
      (node (ref "U2") (pin "5") (pinfunction "2B_5") (pintype "input"))
    )
    (net (code "27") (name "Net-(NOT1B-Y2)") (class "Default")
      (node (ref "NOT1") (pin "4") (pinfunction "Y2_4") (pintype "output"))
      (node (ref "PCM1") (pin "1") (pinfunction "G_1") (pintype "passive"))
      (node (ref "R23") (pin "1") (pinfunction "1_1") (pintype "passive"))
    )
    (net (code "28") (name "Net-(U2A-1Y)") (class "Default")
      (node (ref "R20") (pin "1") (pinfunction "1_1") (pintype "passive"))
      (node (ref "U2") (pin "3") (pinfunction "1Y_3") (pintype "output"))
      (node (ref "U2") (pin "4") (pinfunction "2A_4") (pintype "input"))
    )
    (net (code "29") (name "Net-(U2B-2Y)") (class "Default")
      (node (ref "R21") (pin "1") (pinfunction "1_1") (pintype "passive"))
      (node (ref "U2") (pin "12") (pinfunction "4A_12") (pintype "input"))
      (node (ref "U2") (pin "6") (pinfunction "2Y_6") (pintype "output"))
    )
    (net (code "30") (name "Net-(U2C-3Y)") (class "Default")
      (node (ref "R22") (pin "1") (pinfunction "1_1") (pintype "passive"))
      (node (ref "U2") (pin "13") (pinfunction "4B_13") (pintype "input"))
      (node (ref "U2") (pin "8") (pinfunction "3Y_8") (pintype "output"))
    )
    (net (code "31") (name "Net-(U2D-4Y)") (class "Default")
      (node (ref "R6") (pin "1") (pinfunction "1_1") (pintype "passive"))
      (node (ref "U2") (pin "11") (pinfunction "4Y_11") (pintype "output"))
    )
    (net (code "32") (name "unconnected-(RLY1-Pad2)") (class "Default")
      (node (ref "RLY1") (pin "2") (pinfunction "2_2") (pintype "passive+no_connect"))
    )
    (net (code "33") (name "unconnected-(RLY1-Pad5)") (class "Default")
      (node (ref "RLY1") (pin "5") (pinfunction "5_5") (pintype "passive+no_connect"))
    )
    (net (code "34") (name "unconnected-(RLY1-Pad6)") (class "Default")
      (node (ref "RLY1") (pin "6") (pinfunction "6_6") (pintype "passive+no_connect"))
    )
    (net (code "35") (name "unconnected-(RLY1-Pad7)") (class "Default")
      (node (ref "RLY1") (pin "7") (pinfunction "7_7") (pintype "passive+no_connect"))
    )
  )
)
